# Digital_Sensor_Module.net
KiCad netlist of a schematic drawn in Altium Designer
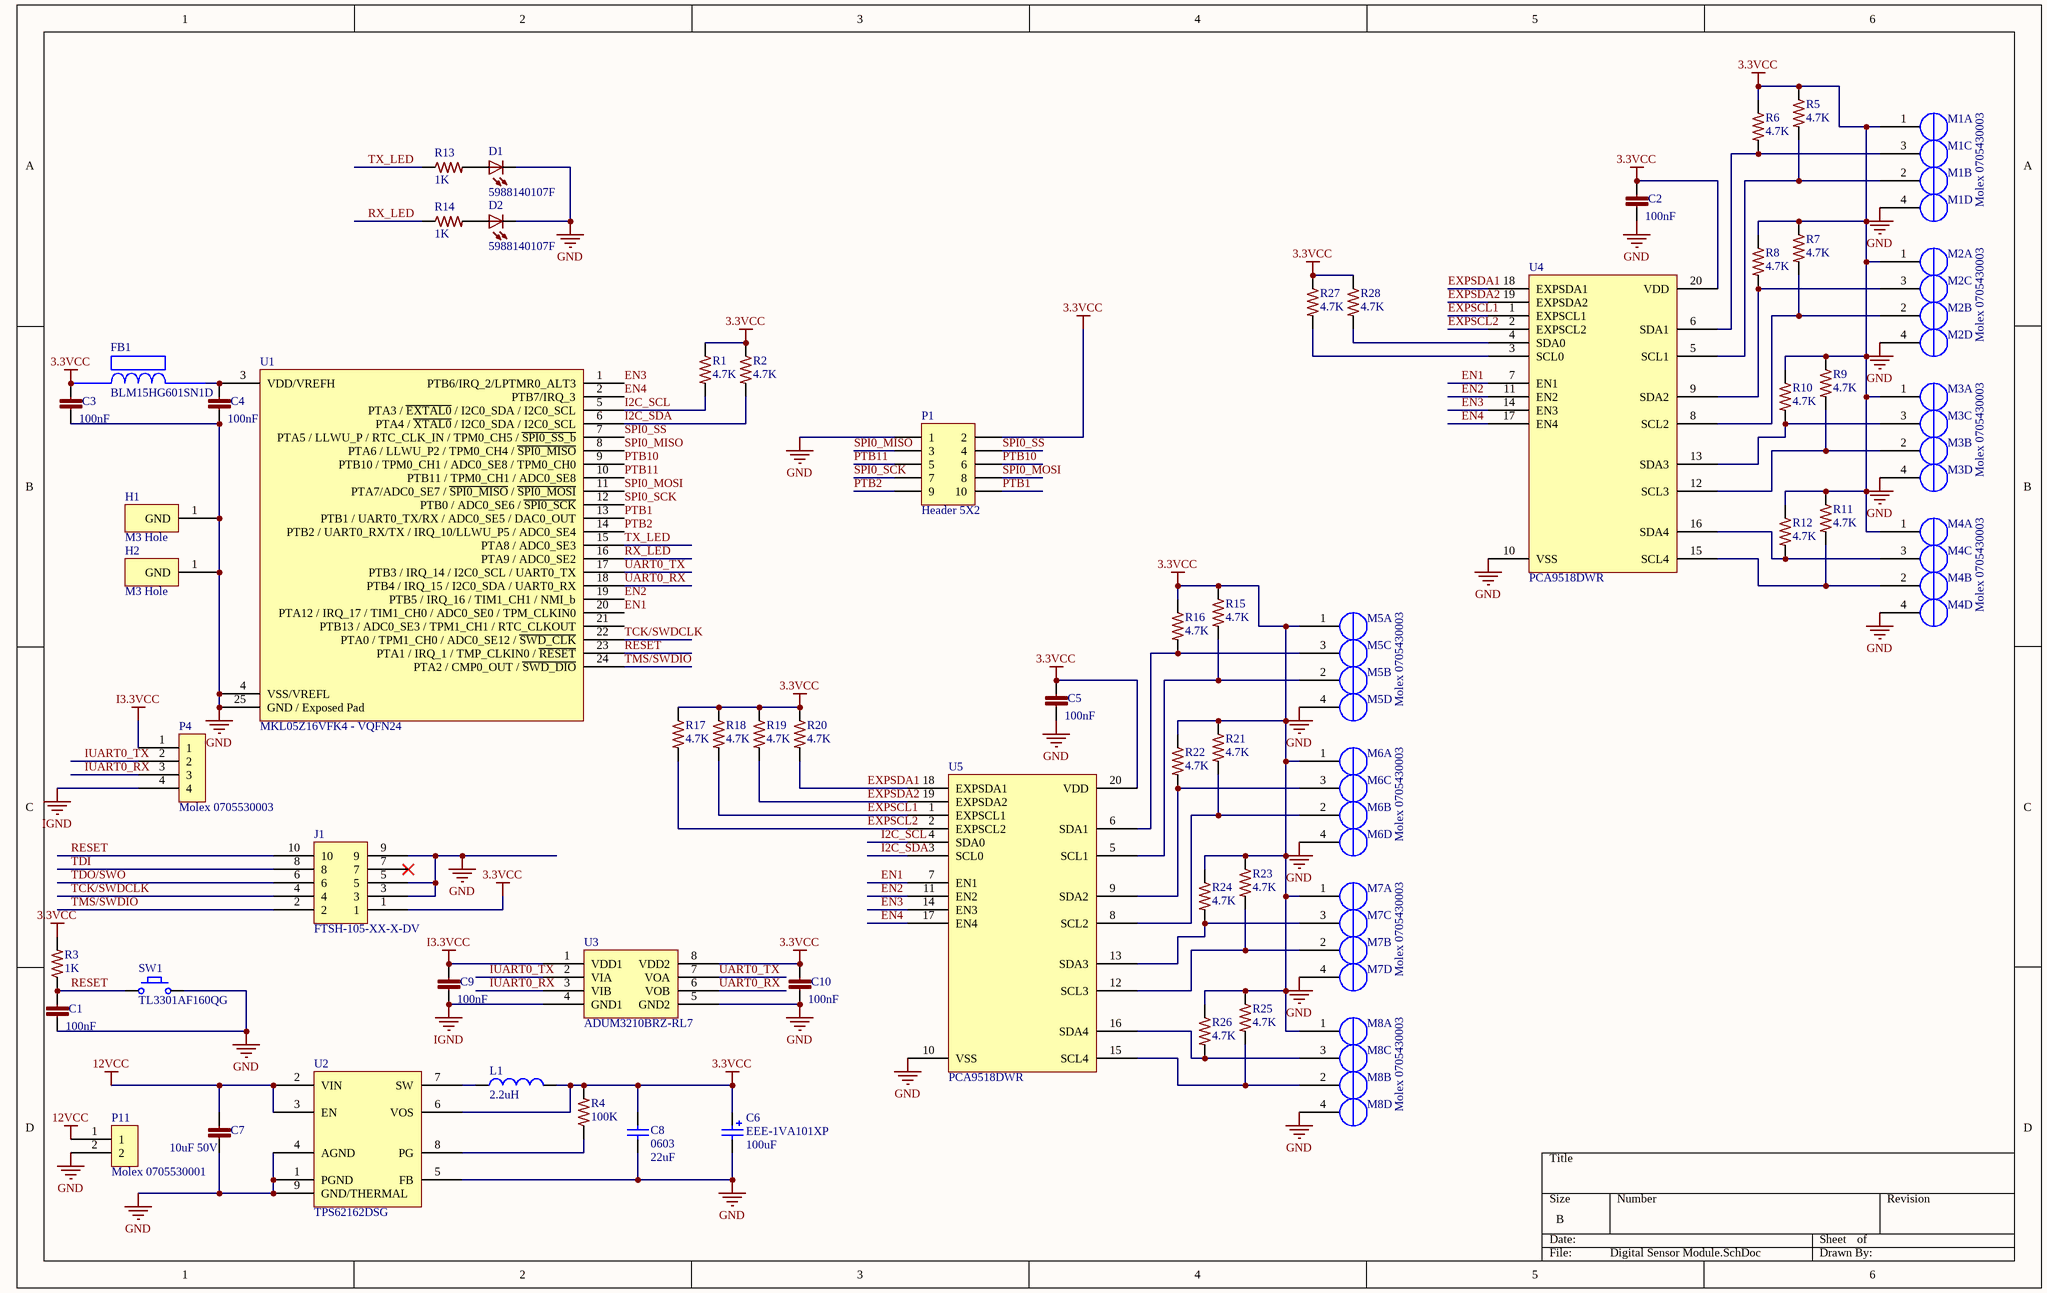
[diagram p0: Digital Sensor Module.SchDoc]

(export (version "E")
  (design (tool "Eeschema 10.0.6"))
  (components
    (comp (ref "C1")
      (value "100nF")
      (footprint "C0402")
      (description "CAP CER 0402 100nF 16V 10% X7R")
      (fields
        (field (name "MANUFACTURERPARTNUMBER") "GRM155R71C104KA88D")
        (field (name "PUBLISHER") "UltiMachine")
      )
      (libsource (lib "3Delight") (part "GRM155R71C104KA88D"))
    )
    (comp (ref "C2")
      (value "100nF")
      (footprint "C0402")
      (description "CAP CER 0402 100nF 16V 10% X7R")
      (fields
        (field (name "MANUFACTURERPARTNUMBER") "GRM155R71C104KA88D")
        (field (name "PUBLISHER") "UltiMachine")
      )
      (libsource (lib "3Delight") (part "GRM155R71C104KA88D"))
    )
    (comp (ref "C3")
      (value "100nF")
      (footprint "C0402")
      (description "CAP CER 0402 100nF 16V 10% X7R")
      (fields
        (field (name "MANUFACTURERPARTNUMBER") "GRM155R71C104KA88D")
        (field (name "PUBLISHER") "UltiMachine")
      )
      (libsource (lib "3Delight") (part "GRM155R71C104KA88D"))
    )
    (comp (ref "C4")
      (value "100nF")
      (footprint "C0402")
      (description "CAP CER 0402 100nF 16V 10% X7R")
      (fields
        (field (name "MANUFACTURERPARTNUMBER") "GRM155R71C104KA88D")
        (field (name "PUBLISHER") "UltiMachine")
      )
      (libsource (lib "3Delight") (part "GRM155R71C104KA88D"))
    )
    (comp (ref "C5")
      (value "100nF")
      (footprint "C0402")
      (description "CAP CER 0402 100nF 16V 10% X7R")
      (fields
        (field (name "MANUFACTURERPARTNUMBER") "GRM155R71C104KA88D")
        (field (name "PUBLISHER") "UltiMachine")
      )
      (libsource (lib "3Delight") (part "GRM155R71C104KA88D"))
    )
    (comp (ref "C6")
      (value "EEE-1VA101XP")
      (footprint "EEE-1VA101XP")
      (description "CAP ALUM 100UF 35V 20% SMD")
      (fields (field (name "DIGIKEY PART #") "PCE3951CT-ND") (field (name "ALTIUM_VALUE") "100uF"))
      (libsource (lib "Tigershark3D") (part "EEE-1VA101XP"))
    )
    (comp (ref "C7")
      (value "10uF 50V")
      (footprint "C1206")
      (description "CAP CER 10UF 50V 10% X5R 1206")
      (fields
        (field (name "MANUFACTURER") "Samsung")
        (field (name "MANUFACTURERPARTNUMBER") "CL31A106KBHNNNE")
        (field (name "PUBLISHER") "UltiMachine")
      )
      (libsource (lib "Tigershark3D") (part "CL31A106KBHNNNE"))
    )
    (comp (ref "C8")
      (value "0603")
      (footprint "C0805")
      (description "CAP CER 22UF 6.3V 10% X5R 0805")
      (fields
        (field (name "MFR PART #") "CL21A226KQQNNNE")
        (field (name "MFR") "Samsung")
        (field (name "ALTIUM_VALUE") "22uF")
      )
      (libsource (lib "Sensor Package") (part "CL21A226KQQNNNE"))
    )
    (comp (ref "C9")
      (value "100nF")
      (footprint "C0402")
      (description "CAP CER 0402 100nF 16V 10% X7R")
      (fields
        (field (name "MANUFACTURERPARTNUMBER") "GRM155R71C104KA88D")
        (field (name "PUBLISHER") "UltiMachine")
      )
      (libsource (lib "3Delight") (part "GRM155R71C104KA88D"))
    )
    (comp (ref "C10")
      (value "100nF")
      (footprint "C0402")
      (description "CAP CER 0402 100nF 16V 10% X7R")
      (fields
        (field (name "MANUFACTURERPARTNUMBER") "GRM155R71C104KA88D")
        (field (name "PUBLISHER") "UltiMachine")
      )
      (libsource (lib "3Delight") (part "GRM155R71C104KA88D"))
    )
    (comp (ref "D1")
      (value "5988140107F")
      (footprint "LED2012120")
      (description "LED 0805 Yellow")
      (fields (field (name "PUBLISHER") "UltiMachine"))
      (libsource (lib "Tigershark3D") (part "5988140107F"))
    )
    (comp (ref "D2")
      (value "5988140107F")
      (footprint "LED2012120")
      (description "LED 0805 Yellow")
      (fields (field (name "PUBLISHER") "UltiMachine"))
      (libsource (lib "Tigershark3D") (part "5988140107F"))
    )
    (comp (ref "FB1")
      (value "BLM15HG601SN1D")
      (footprint "BLM18PG121SN1D")
      (libsource (lib "AHD Part Library") (part "BLM15HG601SN1D"))
    )
    (comp (ref "H1")
      (value "M3 Hole")
      (footprint "Hole-3mm")
      (description "3mm Hole")
      (libsource (lib "Sensor Package") (part "Hole"))
    )
    (comp (ref "H2")
      (value "M3 Hole")
      (footprint "Hole-3mm")
      (description "3mm Hole")
      (libsource (lib "Sensor Package") (part "Hole"))
    )
    (comp (ref "J1")
      (value "FTSH-105-XX-X-DV")
      (footprint "FTSH-105-XX-X-DV")
      (libsource (lib "Adams Altium Library") (part "ARM Cortex JTAG-DEBUG Header"))
    )
    (comp (ref "L1")
      (value "2.2uH")
      (footprint "VLS252012T-2R2M1R3")
      (description "VLS252012T-2R2M1R3")
      (fields (field (name "MFR") "TDK Corporation") (field (name "PUBLISHER") "Adam Vadala-Roth"))
      (libsource (lib "Sensor Package") (part "VLS252012T-2R2M1R3"))
    )
    (comp (ref "M1")
      (value "Molex 0705430003")
      (footprint "4POL254")
      (description "Molex 4 Pin Clip Connector")
      (libsource (lib "ZMBo Schematic Library") (part "Molex 0705430003 Alt"))
    )
    (comp (ref "M2")
      (value "Molex 0705430003")
      (footprint "4POL254")
      (description "Molex 4 Pin Clip Connector")
      (libsource (lib "ZMBo Schematic Library") (part "Molex 0705430003 Alt"))
    )
    (comp (ref "M3")
      (value "Molex 0705430003")
      (footprint "4POL254")
      (description "Molex 4 Pin Clip Connector")
      (libsource (lib "ZMBo Schematic Library") (part "Molex 0705430003 Alt"))
    )
    (comp (ref "M4")
      (value "Molex 0705430003")
      (footprint "Molex 0705430003")
      (description "Molex 4 Pin Clip Connector")
      (libsource (lib "ZMBo Schematic Library") (part "Molex 0705430003 Alt"))
    )
    (comp (ref "M5")
      (value "Molex 0705430003")
      (footprint "4POL254")
      (description "Molex 4 Pin Clip Connector")
      (libsource (lib "ZMBo Schematic Library") (part "Molex 0705430003 Alt"))
    )
    (comp (ref "M6")
      (value "Molex 0705430003")
      (footprint "4POL254")
      (description "Molex 4 Pin Clip Connector")
      (libsource (lib "ZMBo Schematic Library") (part "Molex 0705430003 Alt"))
    )
    (comp (ref "M7")
      (value "Molex 0705430003")
      (footprint "Molex 0705430003")
      (description "Molex 4 Pin Clip Connector")
      (libsource (lib "ZMBo Schematic Library") (part "Molex 0705430003 Alt"))
    )
    (comp (ref "M8")
      (value "Molex 0705430003")
      (footprint "4POL254")
      (description "Molex 4 Pin Clip Connector")
      (libsource (lib "ZMBo Schematic Library") (part "Molex 0705430003 Alt"))
    )
    (comp (ref "P1")
      (value "Header 5X2")
      (footprint "HDR2X5")
      (description "Header, 5-Pin, Dual row")
      (fields (field (name "PUBLISHER") "Altium Limited"))
      (libsource (lib "Miscellaneous Connectors") (part "Header 5X2"))
    )
    (comp (ref "P4")
      (value "Molex 0705530003")
      (footprint "0705530003")
      (description "Molex 0705530003 Right Angle 2.54mm Shrouded Header")
      (fields (field (name "MFR") "Molex"))
      (libsource (lib "Sensor Package") (part "0705530003"))
    )
    (comp (ref "P11")
      (value "Molex 0705530001")
      (footprint "0705530001")
      (description "Molex 0705530002 Right Angle 2.54mm Shrouded Header")
      (fields (field (name "MFR") "Molex"))
      (libsource (lib "Sensor Package") (part "0705530001"))
    )
    (comp (ref "R1")
      (value "4.7K")
      (footprint "R0603")
      (description "RES 0603 4.7K 100mW 1%")
      (fields (field (name "MANUFACTURERPARTNUMBER") "ERJ3EKF4701V") (field (name "PUBLISHER") "UltiMachine"))
      (libsource (lib "Tigershark3D") (part "ERJ3EKF4701V"))
    )
    (comp (ref "R2")
      (value "4.7K")
      (footprint "R0603")
      (description "RES 0603 4.7K 100mW 1%")
      (fields (field (name "MANUFACTURERPARTNUMBER") "ERJ3EKF4701V") (field (name "PUBLISHER") "UltiMachine"))
      (libsource (lib "Tigershark3D") (part "ERJ3EKF4701V"))
    )
    (comp (ref "R3")
      (value "1K")
      (footprint "R0603")
      (description "RES 0603 1K 100mW 1%")
      (fields
        (field (name "MANUFACTURERPARTNUMBER") "ERJ-3EKF1001V")
        (field (name "PUBLISHER") "UltiMachine")
      )
      (libsource (lib "3Delight") (part "ERJ-3EKF1001V"))
    )
    (comp (ref "R4")
      (value "100K")
      (footprint "R0603")
      (description "RES 100K OHM 1/10W 1% 0603 SMD")
      (fields
        (field (name "MANUFACTURERPARTNUMBER") "RC0603FR-07100KL")
        (field (name "PUBLISHER") "UltiMachine")
      )
      (libsource (lib "3Delight") (part "RC0603FR-07100KL"))
    )
    (comp (ref "R5")
      (value "4.7K")
      (footprint "R0603")
      (description "RES 0603 4.7K 100mW 1%")
      (fields (field (name "MANUFACTURERPARTNUMBER") "ERJ3EKF4701V") (field (name "PUBLISHER") "UltiMachine"))
      (libsource (lib "Tigershark3D") (part "ERJ3EKF4701V"))
    )
    (comp (ref "R6")
      (value "4.7K")
      (footprint "R0603")
      (description "RES 0603 4.7K 100mW 1%")
      (fields (field (name "MANUFACTURERPARTNUMBER") "ERJ3EKF4701V") (field (name "PUBLISHER") "UltiMachine"))
      (libsource (lib "Tigershark3D") (part "ERJ3EKF4701V"))
    )
    (comp (ref "R7")
      (value "4.7K")
      (footprint "R0603")
      (description "RES 0603 4.7K 100mW 1%")
      (fields (field (name "MANUFACTURERPARTNUMBER") "ERJ3EKF4701V") (field (name "PUBLISHER") "UltiMachine"))
      (libsource (lib "Tigershark3D") (part "ERJ3EKF4701V"))
    )
    (comp (ref "R8")
      (value "4.7K")
      (footprint "R0603")
      (description "RES 0603 4.7K 100mW 1%")
      (fields (field (name "MANUFACTURERPARTNUMBER") "ERJ3EKF4701V") (field (name "PUBLISHER") "UltiMachine"))
      (libsource (lib "Tigershark3D") (part "ERJ3EKF4701V"))
    )
    (comp (ref "R9")
      (value "4.7K")
      (footprint "R0603")
      (description "RES 0603 4.7K 100mW 1%")
      (fields (field (name "MANUFACTURERPARTNUMBER") "ERJ3EKF4701V") (field (name "PUBLISHER") "UltiMachine"))
      (libsource (lib "Tigershark3D") (part "ERJ3EKF4701V"))
    )
    (comp (ref "R10")
      (value "4.7K")
      (footprint "R0603")
      (description "RES 0603 4.7K 100mW 1%")
      (fields (field (name "MANUFACTURERPARTNUMBER") "ERJ3EKF4701V") (field (name "PUBLISHER") "UltiMachine"))
      (libsource (lib "Tigershark3D") (part "ERJ3EKF4701V"))
    )
    (comp (ref "R11")
      (value "4.7K")
      (footprint "R0603")
      (description "RES 0603 4.7K 100mW 1%")
      (fields (field (name "MANUFACTURERPARTNUMBER") "ERJ3EKF4701V") (field (name "PUBLISHER") "UltiMachine"))
      (libsource (lib "Tigershark3D") (part "ERJ3EKF4701V"))
    )
    (comp (ref "R12")
      (value "4.7K")
      (footprint "R0603")
      (description "RES 0603 4.7K 100mW 1%")
      (fields (field (name "MANUFACTURERPARTNUMBER") "ERJ3EKF4701V") (field (name "PUBLISHER") "UltiMachine"))
      (libsource (lib "Tigershark3D") (part "ERJ3EKF4701V"))
    )
    (comp (ref "R13")
      (value "1K")
      (footprint "R0603")
      (description "RES 0603 1K 100mW 1%")
      (fields
        (field (name "MANUFACTURERPARTNUMBER") "ERJ-3EKF1001V")
        (field (name "PUBLISHER") "UltiMachine")
      )
      (libsource (lib "Tigershark3D") (part "ERJ-3EKF1001V"))
    )
    (comp (ref "R14")
      (value "1K")
      (footprint "R0603")
      (description "RES 0603 1K 100mW 1%")
      (fields
        (field (name "MANUFACTURERPARTNUMBER") "ERJ-3EKF1001V")
        (field (name "PUBLISHER") "UltiMachine")
      )
      (libsource (lib "Tigershark3D") (part "ERJ-3EKF1001V"))
    )
    (comp (ref "R15")
      (value "4.7K")
      (footprint "R0603")
      (description "RES 0603 4.7K 100mW 1%")
      (fields (field (name "MANUFACTURERPARTNUMBER") "ERJ3EKF4701V") (field (name "PUBLISHER") "UltiMachine"))
      (libsource (lib "Tigershark3D") (part "ERJ3EKF4701V"))
    )
    (comp (ref "R16")
      (value "4.7K")
      (footprint "R0603")
      (description "RES 0603 4.7K 100mW 1%")
      (fields (field (name "MANUFACTURERPARTNUMBER") "ERJ3EKF4701V") (field (name "PUBLISHER") "UltiMachine"))
      (libsource (lib "Tigershark3D") (part "ERJ3EKF4701V"))
    )
    (comp (ref "R17")
      (value "4.7K")
      (footprint "R0603")
      (description "RES 0603 4.7K 100mW 1%")
      (fields (field (name "MANUFACTURERPARTNUMBER") "ERJ3EKF4701V") (field (name "PUBLISHER") "UltiMachine"))
      (libsource (lib "Tigershark3D") (part "ERJ3EKF4701V"))
    )
    (comp (ref "R18")
      (value "4.7K")
      (footprint "R0603")
      (description "RES 0603 4.7K 100mW 1%")
      (fields (field (name "MANUFACTURERPARTNUMBER") "ERJ3EKF4701V") (field (name "PUBLISHER") "UltiMachine"))
      (libsource (lib "Tigershark3D") (part "ERJ3EKF4701V"))
    )
    (comp (ref "R19")
      (value "4.7K")
      (footprint "R0603")
      (description "RES 0603 4.7K 100mW 1%")
      (fields (field (name "MANUFACTURERPARTNUMBER") "ERJ3EKF4701V") (field (name "PUBLISHER") "UltiMachine"))
      (libsource (lib "Tigershark3D") (part "ERJ3EKF4701V"))
    )
    (comp (ref "R20")
      (value "4.7K")
      (footprint "R0603")
      (description "RES 0603 4.7K 100mW 1%")
      (fields (field (name "MANUFACTURERPARTNUMBER") "ERJ3EKF4701V") (field (name "PUBLISHER") "UltiMachine"))
      (libsource (lib "Tigershark3D") (part "ERJ3EKF4701V"))
    )
    (comp (ref "R21")
      (value "4.7K")
      (footprint "R0603")
      (description "RES 0603 4.7K 100mW 1%")
      (fields (field (name "MANUFACTURERPARTNUMBER") "ERJ3EKF4701V") (field (name "PUBLISHER") "UltiMachine"))
      (libsource (lib "Tigershark3D") (part "ERJ3EKF4701V"))
    )
    (comp (ref "R22")
      (value "4.7K")
      (footprint "R0603")
      (description "RES 0603 4.7K 100mW 1%")
      (fields (field (name "MANUFACTURERPARTNUMBER") "ERJ3EKF4701V") (field (name "PUBLISHER") "UltiMachine"))
      (libsource (lib "Tigershark3D") (part "ERJ3EKF4701V"))
    )
    (comp (ref "R23")
      (value "4.7K")
      (footprint "R0603")
      (description "RES 0603 4.7K 100mW 1%")
      (fields (field (name "MANUFACTURERPARTNUMBER") "ERJ3EKF4701V") (field (name "PUBLISHER") "UltiMachine"))
      (libsource (lib "Tigershark3D") (part "ERJ3EKF4701V"))
    )
    (comp (ref "R24")
      (value "4.7K")
      (footprint "R0603")
      (description "RES 0603 4.7K 100mW 1%")
      (fields (field (name "MANUFACTURERPARTNUMBER") "ERJ3EKF4701V") (field (name "PUBLISHER") "UltiMachine"))
      (libsource (lib "Tigershark3D") (part "ERJ3EKF4701V"))
    )
    (comp (ref "R25")
      (value "4.7K")
      (footprint "R0603")
      (description "RES 0603 4.7K 100mW 1%")
      (fields (field (name "MANUFACTURERPARTNUMBER") "ERJ3EKF4701V") (field (name "PUBLISHER") "UltiMachine"))
      (libsource (lib "Tigershark3D") (part "ERJ3EKF4701V"))
    )
    (comp (ref "R26")
      (value "4.7K")
      (footprint "R0603")
      (description "RES 0603 4.7K 100mW 1%")
      (fields (field (name "MANUFACTURERPARTNUMBER") "ERJ3EKF4701V") (field (name "PUBLISHER") "UltiMachine"))
      (libsource (lib "Tigershark3D") (part "ERJ3EKF4701V"))
    )
    (comp (ref "R27")
      (value "4.7K")
      (footprint "R0603")
      (description "RES 0603 4.7K 100mW 1%")
      (fields (field (name "MANUFACTURERPARTNUMBER") "ERJ3EKF4701V") (field (name "PUBLISHER") "UltiMachine"))
      (libsource (lib "Tigershark3D") (part "ERJ3EKF4701V"))
    )
    (comp (ref "R28")
      (value "4.7K")
      (footprint "R0603")
      (description "RES 0603 4.7K 100mW 1%")
      (fields (field (name "MANUFACTURERPARTNUMBER") "ERJ3EKF4701V") (field (name "PUBLISHER") "UltiMachine"))
      (libsource (lib "Tigershark3D") (part "ERJ3EKF4701V"))
    )
    (comp (ref "SW1")
      (value "TL3301AF160QG")
      (footprint "TL3301AF160QG")
      (libsource (lib "MongoosMini") (part "TL3301AF160QG"))
    )
    (comp (ref "U1")
      (value "MKL05Z16VFK4 - VQFN24")
      (footprint "98ASA00474D")
      (description "ARM Cortex M0+")
      (libsource (lib "Encoder Fin") (part "MKL05Z16VFK4 - 24 Pin VQFN"))
    )
    (comp (ref "U2")
      (value "TPS62162DSG")
      (footprint "DSG8-1600X900TP")
      (libsource (lib "Adams Altium Library") (part "TPS62162SOP"))
    )
    (comp (ref "U3")
      (value "ADUM3210BRZ-RL7")
      (footprint "ADUM3210BRZ-RL7")
      (description "DGTL ISO 2.5KV GEN PURP 8SOIC")
      (fields (field (name "MFR") "Analog Devices"))
      (libsource (lib "Sensor Package") (part "ADUM3210BRZ-RL7"))
    )
    (comp (ref "U4")
      (value "PCA9518DWR")
      (footprint "PCA9518DWR")
      (description "IC EXPANDABLE 5CH I2C HUB 20SOIC")
      (fields (field (name "MFR") "Ti"))
      (libsource (lib "Sensor Package") (part "PCA9518DWR"))
    )
    (comp (ref "U5")
      (value "PCA9518DWR")
      (footprint "PCA9518DWR")
      (description "IC EXPANDABLE 5CH I2C HUB 20SOIC")
      (fields (field (name "MFR") "Ti"))
      (libsource (lib "Sensor Package") (part "PCA9518DWR"))
    )
  )
  (nets
    (net (code "1") (name "/EN1") (class "Default")
      (node (ref "U1") (pin "20") (pinfunction "PTA12_/_IRQ_17_/_TIM1_CH0_/_ADC0_SE0_/_TPM_CLKIN0_20") (pintype "passive"))
      (node (ref "U4") (pin "7") (pinfunction "EN1_7") (pintype "passive"))
      (node (ref "U5") (pin "7") (pinfunction "EN1_7") (pintype "passive"))
    )
    (net (code "2") (name "/EN2") (class "Default")
      (node (ref "U1") (pin "19") (pinfunction "PTB5_/_IRQ_16_/_TIM1_CH1_/_NMI_b_19") (pintype "passive"))
      (node (ref "U4") (pin "11") (pinfunction "EN2_11") (pintype "passive"))
      (node (ref "U5") (pin "11") (pinfunction "EN2_11") (pintype "passive"))
    )
    (net (code "3") (name "/EN3") (class "Default")
      (node (ref "U1") (pin "1") (pinfunction "PTB6/IRQ_2/LPTMR0_ALT3_1") (pintype "passive"))
      (node (ref "U4") (pin "14") (pinfunction "EN3_14") (pintype "passive"))
      (node (ref "U5") (pin "14") (pinfunction "EN3_14") (pintype "passive"))
    )
    (net (code "4") (name "/EN4") (class "Default")
      (node (ref "U1") (pin "2") (pinfunction "PTB7/IRQ_3_2") (pintype "passive"))
      (node (ref "U4") (pin "17") (pinfunction "EN4_17") (pintype "passive"))
      (node (ref "U5") (pin "17") (pinfunction "EN4_17") (pintype "passive"))
    )
    (net (code "5") (name "/EXPSCL1") (class "Default")
      (node (ref "R18") (pin "2") (pinfunction "2_2") (pintype "passive"))
      (node (ref "U4") (pin "1") (pinfunction "EXPSCL1_1") (pintype "passive"))
      (node (ref "U5") (pin "1") (pinfunction "EXPSCL1_1") (pintype "passive"))
    )
    (net (code "6") (name "/EXPSCL2") (class "Default")
      (node (ref "R17") (pin "2") (pinfunction "2_2") (pintype "passive"))
      (node (ref "U4") (pin "2") (pinfunction "EXPSCL2_2") (pintype "passive"))
      (node (ref "U5") (pin "2") (pinfunction "EXPSCL2_2") (pintype "passive"))
    )
    (net (code "7") (name "/EXPSDA1") (class "Default")
      (node (ref "R20") (pin "2") (pinfunction "2_2") (pintype "passive"))
      (node (ref "U4") (pin "18") (pinfunction "EXPSDA1_18") (pintype "passive"))
      (node (ref "U5") (pin "18") (pinfunction "EXPSDA1_18") (pintype "passive"))
    )
    (net (code "8") (name "/EXPSDA2") (class "Default")
      (node (ref "R19") (pin "2") (pinfunction "2_2") (pintype "passive"))
      (node (ref "U4") (pin "19") (pinfunction "EXPSDA2_19") (pintype "passive"))
      (node (ref "U5") (pin "19") (pinfunction "EXPSDA2_19") (pintype "passive"))
    )
    (net (code "9") (name "/I2C_SCL") (class "Default")
      (node (ref "R1") (pin "2") (pinfunction "2_2") (pintype "passive"))
      (node (ref "U1") (pin "5") (pinfunction "PTA3_/_~{EXTAL0}_/_I2C0_SDA_/_I2C0_SCL_5") (pintype "passive"))
      (node (ref "U5") (pin "4") (pinfunction "SDA0_4") (pintype "passive"))
    )
    (net (code "10") (name "/I2C_SDA") (class "Default")
      (node (ref "R2") (pin "2") (pinfunction "2_2") (pintype "passive"))
      (node (ref "U1") (pin "6") (pinfunction "PTA4_/_~{XTAL0}_/_I2C0_SDA_/_I2C0_SCL_6") (pintype "passive"))
      (node (ref "U5") (pin "3") (pinfunction "SCL0_3") (pintype "passive"))
    )
    (net (code "11") (name "/IUART0_RX") (class "Default")
      (node (ref "P4") (pin "3") (pinfunction "3_3") (pintype "passive"))
      (node (ref "U3") (pin "3") (pinfunction "VIB_3") (pintype "passive"))
    )
    (net (code "12") (name "/IUART0_TX") (class "Default")
      (node (ref "P4") (pin "2") (pinfunction "2_2") (pintype "passive"))
      (node (ref "U3") (pin "2") (pinfunction "VIA_2") (pintype "passive"))
    )
    (net (code "13") (name "/PTB1") (class "Default")
      (node (ref "P1") (pin "10") (pinfunction "10_10") (pintype "passive"))
      (node (ref "U1") (pin "13") (pinfunction "PTB1_/_UART0_TX/RX_/_ADC0_SE5_/_DAC0_OUT_13") (pintype "passive"))
    )
    (net (code "14") (name "/PTB2") (class "Default")
      (node (ref "P1") (pin "9") (pinfunction "9_9") (pintype "passive"))
      (node (ref "U1") (pin "14") (pinfunction "PTB2_/_UART0_RX/TX_/_IRQ_10/LLWU_P5_/_ADC0_SE4_14") (pintype "passive"))
    )
    (net (code "15") (name "/PTB10") (class "Default")
      (node (ref "P1") (pin "6") (pinfunction "6_6") (pintype "passive"))
      (node (ref "U1") (pin "9") (pinfunction "PTB10_/_TPM0_CH1_/_ADC0_SE8_/_TPM0_CH0_9") (pintype "passive"))
    )
    (net (code "16") (name "/PTB11") (class "Default")
      (node (ref "P1") (pin "5") (pinfunction "5_5") (pintype "passive"))
      (node (ref "U1") (pin "10") (pinfunction "PTB11_/_TPM0_CH1_/_ADC0_SE8_10") (pintype "passive"))
    )
    (net (code "17") (name "/RESET") (class "Default")
      (node (ref "C1") (pin "1") (pinfunction "1_1") (pintype "passive"))
      (node (ref "J1") (pin "10") (pinfunction "10_10") (pintype "passive"))
      (node (ref "R3") (pin "1") (pinfunction "1_1") (pintype "passive"))
      (node (ref "SW1") (pin "1") (pintype "passive"))
      (node (ref "U1") (pin "23") (pinfunction "PTA1_/_IRQ_1_/_TMP_CLKIN0_/_~{RESET}_23") (pintype "passive"))
    )
    (net (code "18") (name "/RX_LED") (class "Default")
      (node (ref "R14") (pin "1") (pinfunction "1_1") (pintype "passive"))
      (node (ref "U1") (pin "16") (pinfunction "PTA9_/_ADC0_SE2_16") (pintype "passive"))
    )
    (net (code "19") (name "/SPI0_MISO") (class "Default")
      (node (ref "P1") (pin "3") (pinfunction "3_3") (pintype "passive"))
      (node (ref "U1") (pin "8") (pinfunction "PTA6_/_LLWU_P2_/_TPM0_CH4_/_~{SPI0_MISO}_8") (pintype "passive"))
    )
    (net (code "20") (name "/SPI0_MOSI") (class "Default")
      (node (ref "P1") (pin "8") (pinfunction "8_8") (pintype "passive"))
      (node (ref "U1") (pin "11") (pinfunction "PTA7/ADC0_SE7_/_~{SPI0_MISO}_/_~{SPI0_MOSI}_11") (pintype "passive"))
    )
    (net (code "21") (name "/SPI0_SCK") (class "Default")
      (node (ref "P1") (pin "7") (pinfunction "7_7") (pintype "passive"))
      (node (ref "U1") (pin "12") (pinfunction "PTB0_/_ADC0_SE6_/_~{SPI0_SCK}_12") (pintype "passive"))
    )
    (net (code "22") (name "/SPI0_SS") (class "Default")
      (node (ref "P1") (pin "4") (pinfunction "4_4") (pintype "passive"))
      (node (ref "U1") (pin "7") (pinfunction "PTA5_/_LLWU_P_/_RTC_CLK_IN_/_TPM0_CH5_/_~{SPI0_SS_b}_7") (pintype "passive"))
    )
    (net (code "23") (name "/TCK{slash}SWDCLK") (class "Default")
      (node (ref "J1") (pin "4") (pinfunction "4_4") (pintype "passive"))
      (node (ref "U1") (pin "22") (pinfunction "PTA0_/_TPM1_CH0_/_ADC0_SE12_/_~{SWD_CLK}_22") (pintype "passive"))
    )
    (net (code "24") (name "/TDI") (class "Default")
      (node (ref "J1") (pin "8") (pinfunction "8_8") (pintype "passive"))
    )
    (net (code "25") (name "/TDO{slash}SWO") (class "Default")
      (node (ref "J1") (pin "6") (pinfunction "6_6") (pintype "passive"))
    )
    (net (code "26") (name "/TMS{slash}SWDIO") (class "Default")
      (node (ref "J1") (pin "2") (pinfunction "2_2") (pintype "passive"))
      (node (ref "U1") (pin "24") (pinfunction "PTA2_/_CMP0_OUT_/_~{SWD_DIO}_24") (pintype "passive"))
    )
    (net (code "27") (name "/TX_LED") (class "Default")
      (node (ref "R13") (pin "1") (pinfunction "1_1") (pintype "passive"))
      (node (ref "U1") (pin "15") (pinfunction "PTA8_/_ADC0_SE3_15") (pintype "passive"))
    )
    (net (code "28") (name "/UART0_RX") (class "Default")
      (node (ref "U1") (pin "18") (pinfunction "PTB4_/_IRQ_15_/_I2C0_SDA_/_UART0_RX_18") (pintype "passive"))
      (node (ref "U3") (pin "6") (pinfunction "VOB_6") (pintype "passive"))
    )
    (net (code "29") (name "/UART0_TX") (class "Default")
      (node (ref "U1") (pin "17") (pinfunction "PTB3_/_IRQ_14_/_I2C0_SCL_/_UART0_TX_17") (pintype "passive"))
      (node (ref "U3") (pin "7") (pinfunction "VOA_7") (pintype "passive"))
    )
    (net (code "30") (name "3.3VCC") (class "Default")
      (node (ref "C10") (pin "1") (pinfunction "1_1") (pintype "passive"))
      (node (ref "C2") (pin "1") (pinfunction "1_1") (pintype "passive"))
      (node (ref "C3") (pin "1") (pinfunction "1_1") (pintype "passive"))
      (node (ref "C5") (pin "1") (pinfunction "1_1") (pintype "passive"))
      (node (ref "C6") (pin "1") (pinfunction "1_1") (pintype "passive"))
      (node (ref "C8") (pin "2") (pinfunction "2_2") (pintype "passive"))
      (node (ref "FB1") (pin "1") (pinfunction "1_1") (pintype "passive"))
      (node (ref "J1") (pin "1") (pinfunction "1_1") (pintype "passive"))
      (node (ref "L1") (pin "2") (pinfunction "2_2") (pintype "passive"))
      (node (ref "M1") (pin "1") (pinfunction "OUT2B_1") (pintype "passive"))
      (node (ref "M2") (pin "1") (pinfunction "OUT2B_1") (pintype "passive"))
      (node (ref "M3") (pin "1") (pinfunction "OUT2B_1") (pintype "passive"))
      (node (ref "M4") (pin "1") (pinfunction "OUT2B_1") (pintype "passive"))
      (node (ref "M5") (pin "1") (pinfunction "OUT2B_1") (pintype "passive"))
      (node (ref "M6") (pin "1") (pinfunction "OUT2B_1") (pintype "passive"))
      (node (ref "M7") (pin "1") (pinfunction "OUT2B_1") (pintype "passive"))
      (node (ref "M8") (pin "1") (pinfunction "OUT2B_1") (pintype "passive"))
      (node (ref "P1") (pin "2") (pinfunction "2_2") (pintype "passive"))
      (node (ref "R1") (pin "1") (pinfunction "1_1") (pintype "passive"))
      (node (ref "R10") (pin "1") (pinfunction "1_1") (pintype "passive"))
      (node (ref "R11") (pin "1") (pinfunction "1_1") (pintype "passive"))
      (node (ref "R12") (pin "1") (pinfunction "1_1") (pintype "passive"))
      (node (ref "R15") (pin "1") (pinfunction "1_1") (pintype "passive"))
      (node (ref "R16") (pin "1") (pinfunction "1_1") (pintype "passive"))
      (node (ref "R17") (pin "1") (pinfunction "1_1") (pintype "passive"))
      (node (ref "R18") (pin "1") (pinfunction "1_1") (pintype "passive"))
      (node (ref "R19") (pin "1") (pinfunction "1_1") (pintype "passive"))
      (node (ref "R2") (pin "1") (pinfunction "1_1") (pintype "passive"))
      (node (ref "R20") (pin "1") (pinfunction "1_1") (pintype "passive"))
      (node (ref "R21") (pin "1") (pinfunction "1_1") (pintype "passive"))
      (node (ref "R22") (pin "1") (pinfunction "1_1") (pintype "passive"))
      (node (ref "R23") (pin "1") (pinfunction "1_1") (pintype "passive"))
      (node (ref "R24") (pin "1") (pinfunction "1_1") (pintype "passive"))
      (node (ref "R25") (pin "1") (pinfunction "1_1") (pintype "passive"))
      (node (ref "R26") (pin "1") (pinfunction "1_1") (pintype "passive"))
      (node (ref "R27") (pin "1") (pinfunction "1_1") (pintype "passive"))
      (node (ref "R28") (pin "1") (pinfunction "1_1") (pintype "passive"))
      (node (ref "R3") (pin "2") (pinfunction "2_2") (pintype "passive"))
      (node (ref "R4") (pin "2") (pinfunction "2_2") (pintype "passive"))
      (node (ref "R5") (pin "1") (pinfunction "1_1") (pintype "passive"))
      (node (ref "R6") (pin "1") (pinfunction "1_1") (pintype "passive"))
      (node (ref "R7") (pin "1") (pinfunction "1_1") (pintype "passive"))
      (node (ref "R8") (pin "1") (pinfunction "1_1") (pintype "passive"))
      (node (ref "R9") (pin "1") (pinfunction "1_1") (pintype "passive"))
      (node (ref "U2") (pin "6") (pinfunction "VOS_6") (pintype "passive"))
      (node (ref "U3") (pin "8") (pinfunction "VDD2_8") (pintype "passive"))
      (node (ref "U4") (pin "20") (pinfunction "VDD_20") (pintype "passive"))
      (node (ref "U5") (pin "20") (pinfunction "VDD_20") (pintype "passive"))
    )
    (net (code "31") (name "12VCC") (class "Default")
      (node (ref "C7") (pin "1") (pinfunction "1_1") (pintype "passive"))
      (node (ref "P11") (pin "1") (pinfunction "1_1") (pintype "passive"))
      (node (ref "U2") (pin "2") (pinfunction "VIN_2") (pintype "passive"))
      (node (ref "U2") (pin "3") (pinfunction "EN_3") (pintype "passive"))
    )
    (net (code "32") (name "GND") (class "Default")
      (node (ref "C1") (pin "2") (pinfunction "2_2") (pintype "passive"))
      (node (ref "C10") (pin "2") (pinfunction "2_2") (pintype "passive"))
      (node (ref "C2") (pin "2") (pinfunction "2_2") (pintype "passive"))
      (node (ref "C3") (pin "2") (pinfunction "2_2") (pintype "passive"))
      (node (ref "C4") (pin "2") (pinfunction "2_2") (pintype "passive"))
      (node (ref "C5") (pin "2") (pinfunction "2_2") (pintype "passive"))
      (node (ref "C6") (pin "2") (pinfunction "2_2") (pintype "passive"))
      (node (ref "C7") (pin "2") (pinfunction "2_2") (pintype "passive"))
      (node (ref "C8") (pin "1") (pinfunction "1_1") (pintype "passive"))
      (node (ref "D1") (pin "C") (pinfunction "C_C") (pintype "passive"))
      (node (ref "D2") (pin "C") (pinfunction "C_C") (pintype "passive"))
      (node (ref "H1") (pin "1") (pinfunction "GND_1") (pintype "passive"))
      (node (ref "H2") (pin "1") (pinfunction "GND_1") (pintype "passive"))
      (node (ref "J1") (pin "3") (pinfunction "3_3") (pintype "passive"))
      (node (ref "J1") (pin "5") (pinfunction "5_5") (pintype "passive"))
      (node (ref "J1") (pin "9") (pinfunction "9_9") (pintype "passive"))
      (node (ref "M1") (pin "4") (pinfunction "OUT1B_4") (pintype "passive"))
      (node (ref "M2") (pin "4") (pinfunction "OUT1B_4") (pintype "passive"))
      (node (ref "M3") (pin "4") (pinfunction "OUT1B_4") (pintype "passive"))
      (node (ref "M4") (pin "4") (pinfunction "OUT1B_4") (pintype "passive"))
      (node (ref "M5") (pin "4") (pinfunction "OUT1B_4") (pintype "passive"))
      (node (ref "M6") (pin "4") (pinfunction "OUT1B_4") (pintype "passive"))
      (node (ref "M7") (pin "4") (pinfunction "OUT1B_4") (pintype "passive"))
      (node (ref "M8") (pin "4") (pinfunction "OUT1B_4") (pintype "passive"))
      (node (ref "P1") (pin "1") (pinfunction "1_1") (pintype "passive"))
      (node (ref "P11") (pin "2") (pinfunction "2_2") (pintype "passive"))
      (node (ref "SW1") (pin "2") (pintype "passive"))
      (node (ref "U1") (pin "25") (pinfunction "GND_/_Exposed_Pad_25") (pintype "passive"))
      (node (ref "U1") (pin "4") (pinfunction "VSS/VREFL_4") (pintype "passive"))
      (node (ref "U2") (pin "1") (pinfunction "PGND_1") (pintype "passive"))
      (node (ref "U2") (pin "4") (pinfunction "AGND_4") (pintype "passive"))
      (node (ref "U2") (pin "5") (pinfunction "FB_5") (pintype "passive"))
      (node (ref "U2") (pin "9") (pinfunction "GND/THERMAL_9") (pintype "passive"))
      (node (ref "U3") (pin "5") (pinfunction "GND2_5") (pintype "passive"))
      (node (ref "U4") (pin "10") (pinfunction "VSS_10") (pintype "passive"))
      (node (ref "U5") (pin "10") (pinfunction "VSS_10") (pintype "passive"))
    )
    (net (code "33") (name "I3.3VCC") (class "Default")
      (node (ref "C9") (pin "1") (pinfunction "1_1") (pintype "passive"))
      (node (ref "P4") (pin "1") (pinfunction "1_1") (pintype "passive"))
      (node (ref "U3") (pin "1") (pinfunction "VDD1_1") (pintype "passive"))
    )
    (net (code "34") (name "IGND") (class "Default")
      (node (ref "C9") (pin "2") (pinfunction "2_2") (pintype "passive"))
      (node (ref "P4") (pin "4") (pinfunction "4_4") (pintype "passive"))
      (node (ref "U3") (pin "4") (pinfunction "GND1_4") (pintype "passive"))
    )
    (net (code "35") (name "Net-(D1-PadA)") (class "Default")
      (node (ref "D1") (pin "A") (pinfunction "A_A") (pintype "passive"))
      (node (ref "R13") (pin "2") (pinfunction "2_2") (pintype "passive"))
    )
    (net (code "36") (name "Net-(D2-PadA)") (class "Default")
      (node (ref "D2") (pin "A") (pinfunction "A_A") (pintype "passive"))
      (node (ref "R14") (pin "2") (pinfunction "2_2") (pintype "passive"))
    )
    (net (code "37") (name "Net-(M1B-OUT2A)") (class "Default")
      (node (ref "M1") (pin "2") (pinfunction "OUT2A_2") (pintype "passive"))
      (node (ref "R5") (pin "2") (pinfunction "2_2") (pintype "passive"))
      (node (ref "U4") (pin "5") (pinfunction "SCL1_5") (pintype "passive"))
    )
    (net (code "38") (name "Net-(M1C-OUT1A)") (class "Default")
      (node (ref "M1") (pin "3") (pinfunction "OUT1A_3") (pintype "passive"))
      (node (ref "R6") (pin "2") (pinfunction "2_2") (pintype "passive"))
      (node (ref "U4") (pin "6") (pinfunction "SDA1_6") (pintype "passive"))
    )
    (net (code "39") (name "Net-(M2B-OUT2A)") (class "Default")
      (node (ref "M2") (pin "2") (pinfunction "OUT2A_2") (pintype "passive"))
      (node (ref "R7") (pin "2") (pinfunction "2_2") (pintype "passive"))
      (node (ref "U4") (pin "8") (pinfunction "SCL2_8") (pintype "passive"))
    )
    (net (code "40") (name "Net-(M2C-OUT1A)") (class "Default")
      (node (ref "M2") (pin "3") (pinfunction "OUT1A_3") (pintype "passive"))
      (node (ref "R8") (pin "2") (pinfunction "2_2") (pintype "passive"))
      (node (ref "U4") (pin "9") (pinfunction "SDA2_9") (pintype "passive"))
    )
    (net (code "41") (name "Net-(M3B-OUT2A)") (class "Default")
      (node (ref "M3") (pin "2") (pinfunction "OUT2A_2") (pintype "passive"))
      (node (ref "R9") (pin "2") (pinfunction "2_2") (pintype "passive"))
      (node (ref "U4") (pin "12") (pinfunction "SCL3_12") (pintype "passive"))
    )
    (net (code "42") (name "Net-(M3C-OUT1A)") (class "Default")
      (node (ref "M3") (pin "3") (pinfunction "OUT1A_3") (pintype "passive"))
      (node (ref "R10") (pin "2") (pinfunction "2_2") (pintype "passive"))
      (node (ref "U4") (pin "13") (pinfunction "SDA3_13") (pintype "passive"))
    )
    (net (code "43") (name "Net-(M4B-OUT2A)") (class "Default")
      (node (ref "M4") (pin "2") (pinfunction "OUT2A_2") (pintype "passive"))
      (node (ref "R11") (pin "2") (pinfunction "2_2") (pintype "passive"))
      (node (ref "U4") (pin "15") (pinfunction "SCL4_15") (pintype "passive"))
    )
    (net (code "44") (name "Net-(M4C-OUT1A)") (class "Default")
      (node (ref "M4") (pin "3") (pinfunction "OUT1A_3") (pintype "passive"))
      (node (ref "R12") (pin "2") (pinfunction "2_2") (pintype "passive"))
      (node (ref "U4") (pin "16") (pinfunction "SDA4_16") (pintype "passive"))
    )
    (net (code "45") (name "Net-(M5B-OUT2A)") (class "Default")
      (node (ref "M5") (pin "2") (pinfunction "OUT2A_2") (pintype "passive"))
      (node (ref "R15") (pin "2") (pinfunction "2_2") (pintype "passive"))
      (node (ref "U5") (pin "5") (pinfunction "SCL1_5") (pintype "passive"))
    )
    (net (code "46") (name "Net-(M5C-OUT1A)") (class "Default")
      (node (ref "M5") (pin "3") (pinfunction "OUT1A_3") (pintype "passive"))
      (node (ref "R16") (pin "2") (pinfunction "2_2") (pintype "passive"))
      (node (ref "U5") (pin "6") (pinfunction "SDA1_6") (pintype "passive"))
    )
    (net (code "47") (name "Net-(M6B-OUT2A)") (class "Default")
      (node (ref "M6") (pin "2") (pinfunction "OUT2A_2") (pintype "passive"))
      (node (ref "R21") (pin "2") (pinfunction "2_2") (pintype "passive"))
      (node (ref "U5") (pin "8") (pinfunction "SCL2_8") (pintype "passive"))
    )
    (net (code "48") (name "Net-(M6C-OUT1A)") (class "Default")
      (node (ref "M6") (pin "3") (pinfunction "OUT1A_3") (pintype "passive"))
      (node (ref "R22") (pin "2") (pinfunction "2_2") (pintype "passive"))
      (node (ref "U5") (pin "9") (pinfunction "SDA2_9") (pintype "passive"))
    )
    (net (code "49") (name "Net-(M7B-OUT2A)") (class "Default")
      (node (ref "M7") (pin "2") (pinfunction "OUT2A_2") (pintype "passive"))
      (node (ref "R23") (pin "2") (pinfunction "2_2") (pintype "passive"))
      (node (ref "U5") (pin "12") (pinfunction "SCL3_12") (pintype "passive"))
    )
    (net (code "50") (name "Net-(M7C-OUT1A)") (class "Default")
      (node (ref "M7") (pin "3") (pinfunction "OUT1A_3") (pintype "passive"))
      (node (ref "R24") (pin "2") (pinfunction "2_2") (pintype "passive"))
      (node (ref "U5") (pin "13") (pinfunction "SDA3_13") (pintype "passive"))
    )
    (net (code "51") (name "Net-(M8B-OUT2A)") (class "Default")
      (node (ref "M8") (pin "2") (pinfunction "OUT2A_2") (pintype "passive"))
      (node (ref "R25") (pin "2") (pinfunction "2_2") (pintype "passive"))
      (node (ref "U5") (pin "15") (pinfunction "SCL4_15") (pintype "passive"))
    )
    (net (code "52") (name "Net-(M8C-OUT1A)") (class "Default")
      (node (ref "M8") (pin "3") (pinfunction "OUT1A_3") (pintype "passive"))
      (node (ref "R26") (pin "2") (pinfunction "2_2") (pintype "passive"))
      (node (ref "U5") (pin "16") (pinfunction "SDA4_16") (pintype "passive"))
    )
    (net (code "53") (name "Net-(U1-VDD{slash}VREFH)") (class "Default")
      (node (ref "C4") (pin "1") (pinfunction "1_1") (pintype "passive"))
      (node (ref "FB1") (pin "2") (pinfunction "2_2") (pintype "passive"))
      (node (ref "U1") (pin "3") (pinfunction "VDD/VREFH_3") (pintype "passive"))
    )
    (net (code "54") (name "Net-(U2-PG)") (class "Default")
      (node (ref "R4") (pin "1") (pinfunction "1_1") (pintype "passive"))
      (node (ref "U2") (pin "8") (pinfunction "PG_8") (pintype "passive"))
    )
    (net (code "55") (name "Net-(U2-SW)") (class "Default")
      (node (ref "L1") (pin "1") (pinfunction "1_1") (pintype "passive"))
      (node (ref "U2") (pin "7") (pinfunction "SW_7") (pintype "passive"))
    )
    (net (code "56") (name "Net-(U4-SCL0)") (class "Default")
      (node (ref "R27") (pin "2") (pinfunction "2_2") (pintype "passive"))
      (node (ref "U4") (pin "3") (pinfunction "SCL0_3") (pintype "passive"))
    )
    (net (code "57") (name "Net-(U4-SDA0)") (class "Default")
      (node (ref "R28") (pin "2") (pinfunction "2_2") (pintype "passive"))
      (node (ref "U4") (pin "4") (pinfunction "SDA0_4") (pintype "passive"))
    )
    (net (code "58") (name "unconnected-(J1-Pad7)") (class "Default")
      (node (ref "J1") (pin "7") (pinfunction "7_7") (pintype "passive+no_connect"))
    )
    (net (code "59") (name "unconnected-(U1-PTB13_{slash}_ADC0_SE3_{slash}_TPM1_CH1_{slash}_RTC_CLKOUT-Pad21)") (class "Default")
      (node (ref "U1") (pin "21") (pinfunction "PTB13_/_ADC0_SE3_/_TPM1_CH1_/_RTC_CLKOUT_21") (pintype "passive"))
    )
  )
)
